# FE.net
KiCad netlist of a schematic drawn in Altium Designer
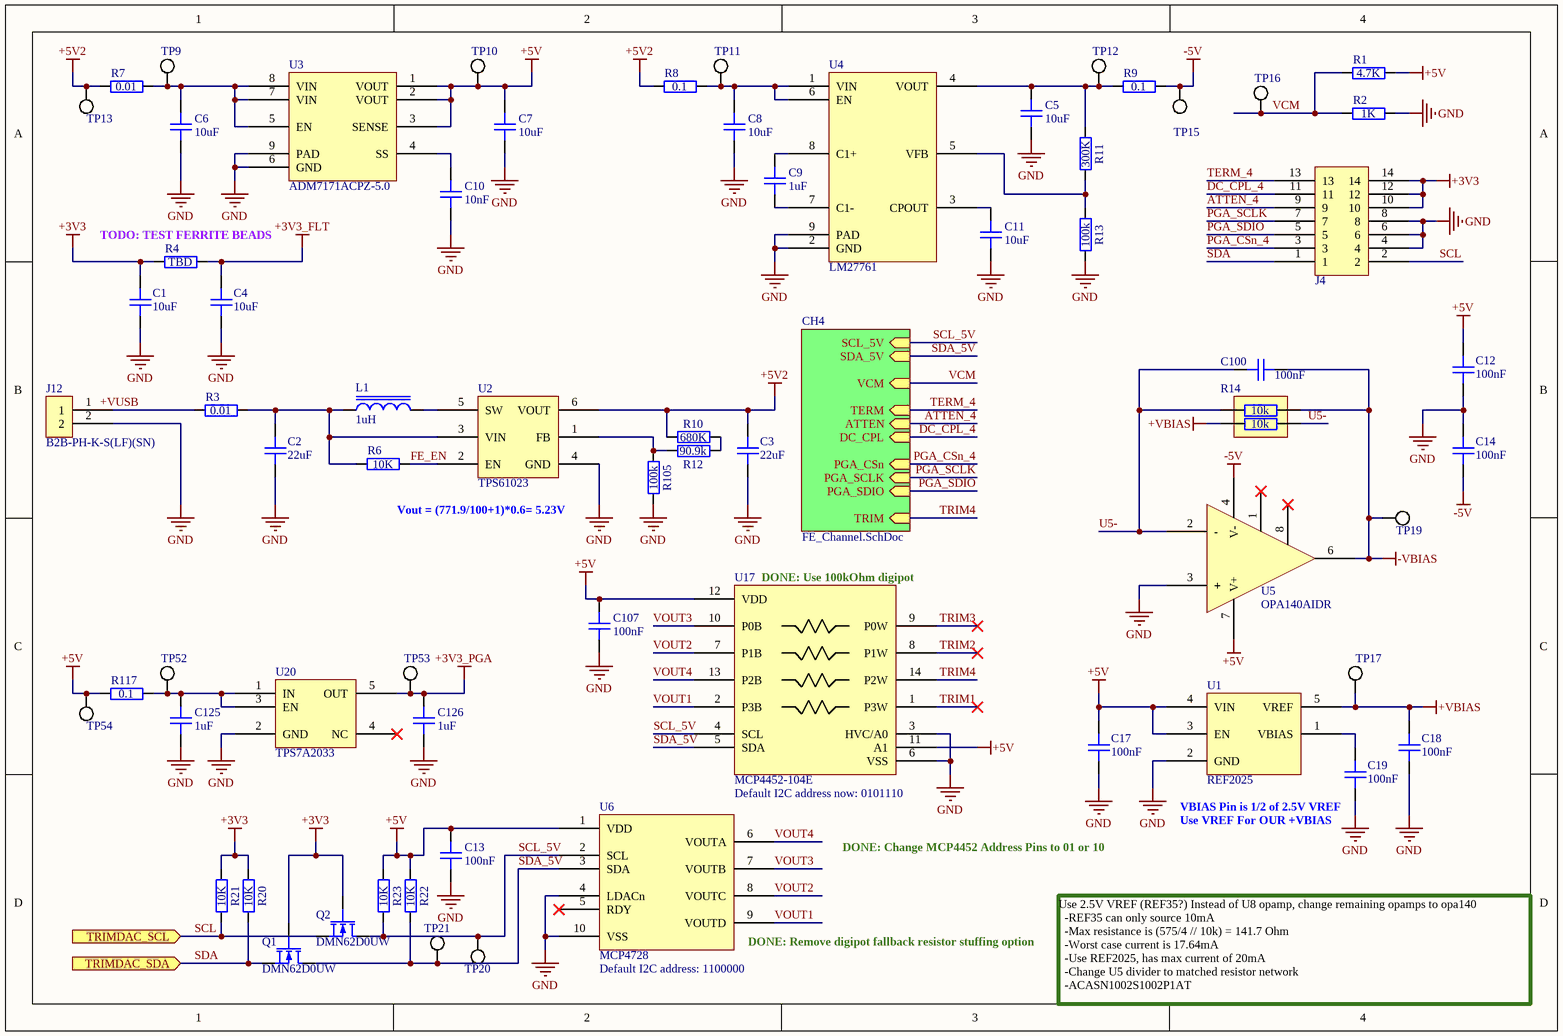
[diagram p0: FE.SchDoc]

(export (version "E")
  (design (tool "Eeschema 10.0.6"))
  (components
    (comp (ref "C1")
      (value "10uF")
      (footprint "GEN_C_0603")
      (fields
        (field (name "MANUFACTURER") "Murata")
        (field (name "HOUSE PART NUMBER") "C-10uF-0603-002")
        (field (name "MANUFACTURER PART NUMBER") "GRM188R61A106ME69D")
      )
      (libsource (lib "DSO") (part "CAP 10uF 10V X5R 0603"))
    )
    (comp (ref "C2")
      (value "22uF")
      (footprint "GEN_C_0805")
      (fields
        (field (name "HOUSE PART NUMBER") "C-22uF-0805-002")
        (field (name "MANUFACTURER") "Murata")
        (field (name "MANUFACTURER PART NUMBER") "GRM21BR61E226ME44L")
      )
      (libsource (lib "DSO") (part "CAP 22uF 25V X5R 0805"))
    )
    (comp (ref "C3")
      (value "22uF")
      (footprint "GEN_C_0805")
      (fields
        (field (name "HOUSE PART NUMBER") "C-22uF-0805-002")
        (field (name "MANUFACTURER") "Murata")
        (field (name "MANUFACTURER PART NUMBER") "GRM21BR61E226ME44L")
      )
      (libsource (lib "DSO") (part "CAP 22uF 25V X5R 0805"))
    )
    (comp (ref "C4")
      (value "10uF")
      (footprint "GEN_C_0603")
      (fields
        (field (name "MANUFACTURER") "Murata")
        (field (name "HOUSE PART NUMBER") "C-10uF-0603-002")
        (field (name "MANUFACTURER PART NUMBER") "GRM188R61A106ME69D")
      )
      (libsource (lib "DSO") (part "CAP 10uF 10V X5R 0603"))
    )
    (comp (ref "C5")
      (value "10uF")
      (footprint "GEN_C_0603")
      (fields
        (field (name "HOUSE PART NUMBER") "C-10uF-0603-002")
        (field (name "MANUFACTURER") "Murata")
        (field (name "MANUFACTURER PART NUMBER") "GRM188R61A106ME69D")
      )
      (libsource (lib "DSO") (part "CAP 10uF 10V X5R 0603"))
    )
    (comp (ref "C6")
      (value "10uF")
      (footprint "GEN_C_0603")
      (fields
        (field (name "HOUSE PART NUMBER") "C-10uF-0603-002")
        (field (name "MANUFACTURER") "Murata")
        (field (name "MANUFACTURER PART NUMBER") "GRM188R61A106ME69D")
      )
      (libsource (lib "DSO") (part "CAP 10uF 10V X5R 0603"))
    )
    (comp (ref "C7")
      (value "10uF")
      (footprint "GEN_C_0603")
      (fields
        (field (name "HOUSE PART NUMBER") "C-10uF-0603-002")
        (field (name "MANUFACTURER") "Murata")
        (field (name "MANUFACTURER PART NUMBER") "GRM188R61A106ME69D")
      )
      (libsource (lib "DSO") (part "CAP 10uF 10V X5R 0603"))
    )
    (comp (ref "C8")
      (value "10uF")
      (footprint "GEN_C_0603")
      (fields
        (field (name "HOUSE PART NUMBER") "C-10uF-0603-002")
        (field (name "MANUFACTURER") "Murata")
        (field (name "MANUFACTURER PART NUMBER") "GRM188R61A106ME69D")
      )
      (libsource (lib "DSO") (part "CAP 10uF 10V X5R 0603"))
    )
    (comp (ref "C9")
      (value "1uF")
      (footprint "GEN_C_0402")
      (fields
        (field (name "MANUFACTURER") "Murata")
        (field (name "MANUFACTURER PART NUMBER") "GRM155R61E105KA12D")
      )
      (libsource (lib "DSO") (part "CAP 1uF 25V X5R 0402"))
    )
    (comp (ref "C10")
      (value "10nF")
      (footprint "GEN_C_0402")
      (fields
        (field (name "MANUFACTURER") "Murata")
        (field (name "HOUSE PART NUMBER") "C-10nF-0402-002")
        (field (name "MANUFACTURER PART NUMBER") "GRM155R71H103KA88J")
      )
      (libsource (lib "DSO") (part "CAP 10nF 50V X7R 0402"))
    )
    (comp (ref "C11")
      (value "10uF")
      (footprint "GEN_C_0603")
      (fields
        (field (name "HOUSE PART NUMBER") "C-10uF-0603-002")
        (field (name "MANUFACTURER") "Murata")
        (field (name "MANUFACTURER PART NUMBER") "GRM188R61A106ME69D")
      )
      (libsource (lib "DSO") (part "CAP 10uF 10V X5R 0603"))
    )
    (comp (ref "C12")
      (value "100nF")
      (footprint "GEN_C_0402")
      (fields
        (field (name "HOUSE PART NUMBER") "C-100nF-0402-002")
        (field (name "MANUFACTURER") "Murata")
        (field (name "MANUFACTURER PART NUMBER") "GCM155R71C104KA55D")
      )
      (libsource (lib "DSO") (part "CAP 100nF 16V X7R 0402"))
    )
    (comp (ref "C13")
      (value "100nF")
      (footprint "GEN_C_0402")
      (fields
        (field (name "HOUSE PART NUMBER") "C-100nF-0402-002")
        (field (name "MANUFACTURER") "Murata")
        (field (name "MANUFACTURER PART NUMBER") "GCM155R71C104KA55D")
      )
      (libsource (lib "DSO") (part "CAP 100nF 16V X7R 0402"))
    )
    (comp (ref "C14")
      (value "100nF")
      (footprint "GEN_C_0402")
      (fields
        (field (name "HOUSE PART NUMBER") "C-100nF-0402-002")
        (field (name "MANUFACTURER") "Murata")
        (field (name "MANUFACTURER PART NUMBER") "GCM155R71C104KA55D")
      )
      (libsource (lib "DSO") (part "CAP 100nF 16V X7R 0402"))
    )
    (comp (ref "C17")
      (value "100nF")
      (footprint "GEN_C_0402")
      (fields
        (field (name "HOUSE PART NUMBER") "C-100nF-0402-002")
        (field (name "MANUFACTURER") "Murata")
        (field (name "MANUFACTURER PART NUMBER") "GCM155R71C104KA55D")
      )
      (libsource (lib "DSO") (part "CAP 100nF 16V X7R 0402"))
    )
    (comp (ref "C18")
      (value "100nF")
      (footprint "GEN_C_0402")
      (fields
        (field (name "HOUSE PART NUMBER") "C-100nF-0402-002")
        (field (name "MANUFACTURER") "Murata")
        (field (name "MANUFACTURER PART NUMBER") "GCM155R71C104KA55D")
      )
      (libsource (lib "DSO") (part "CAP 100nF 16V X7R 0402"))
    )
    (comp (ref "C19")
      (value "100nF")
      (footprint "GEN_C_0402")
      (fields
        (field (name "HOUSE PART NUMBER") "C-100nF-0402-002")
        (field (name "MANUFACTURER") "Murata")
        (field (name "MANUFACTURER PART NUMBER") "GCM155R71C104KA55D")
      )
      (libsource (lib "DSO") (part "CAP 100nF 16V X7R 0402"))
    )
    (comp (ref "C100")
      (value "100nF")
      (footprint "GEN_C_0402")
      (fields
        (field (name "HOUSE PART NUMBER") "C-100nF-0402-002")
        (field (name "MANUFACTURER") "Murata")
        (field (name "MANUFACTURER PART NUMBER") "GCM155R71C104KA55D")
      )
      (libsource (lib "DSO") (part "CAP 100nF 16V X7R 0402"))
    )
    (comp (ref "C107")
      (value "100nF")
      (footprint "GEN_C_0402")
      (fields
        (field (name "HOUSE PART NUMBER") "C-100nF-0402-002")
        (field (name "MANUFACTURER") "Murata")
        (field (name "MANUFACTURER PART NUMBER") "GCM155R71C104KA55D")
      )
      (libsource (lib "DSO") (part "CAP 100nF 16V X7R 0402"))
    )
    (comp (ref "C125")
      (value "1uF")
      (footprint "GEN_C_0402")
      (fields
        (field (name "MANUFACTURER") "Murata")
        (field (name "MANUFACTURER PART NUMBER") "GRM155R61E105KA12D")
      )
      (libsource (lib "DSO") (part "CAP 1uF 25V X5R 0402"))
    )
    (comp (ref "C126")
      (value "1uF")
      (footprint "GEN_C_0402")
      (fields
        (field (name "MANUFACTURER") "Murata")
        (field (name "MANUFACTURER PART NUMBER") "GRM155R61E105KA12D")
      )
      (libsource (lib "DSO") (part "CAP 1uF 25V X5R 0402"))
    )
    (comp (ref "J4")
      (value "2.54mm 2X7 Pin TH")
      (footprint "GEN_2.54mm_2X7_Pin_TH_RA")
      (libsource (lib "DSO") (part "CONN 2.54mm 2X7 Pin TH RA"))
    )
    (comp (ref "J12")
      (value "B2B-PH-K-S(LF)(SN)")
      (footprint "JST_B2B-PH-K-S(LF)(SN)")
      (fields
        (field (name "MANUFACTURER") "JST")
        (field (name "MANUFACTURER PART NUMBER") "B2B-PH-K-S-LF-SN")
      )
      (libsource (lib "DSO") (part "CONN JST PH 2 Pin TH"))
    )
    (comp (ref "L1")
      (value "1uH")
      (footprint "GEN_L_1210")
      (fields
        (field (name "MANUFACTURER") "Murata")
        (field (name "MANUFACTURER PART NUMBER") "1277AS-H-1R0M=P2")
      )
      (libsource (lib "DSO") (part "IND 1uH 3.1A 45 MOHM 1210"))
    )
    (comp (ref "Q1")
      (value "DMN62D0UW")
      (footprint "GEN_SOT_323")
      (fields (field (name "HOUSE PART NUMBER") "DMN62D0UW-7") (field (name "MANUFACTURER") "Diodes"))
      (libsource (lib "DSO") (part "NMOS DMN62D0UW"))
    )
    (comp (ref "Q2")
      (value "DMN62D0UW")
      (footprint "GEN_SOT_323")
      (fields (field (name "HOUSE PART NUMBER") "DMN62D0UW-7") (field (name "MANUFACTURER") "Diodes"))
      (libsource (lib "DSO") (part "NMOS DMN62D0UW"))
    )
    (comp (ref "R1")
      (value "4.7K")
      (footprint "GEN_R_0402")
      (fields
        (field (name "TOLERANCE") "1%")
        (field (name "MANUFACTURER") "Panasonic")
        (field (name "MANUFACTURER PART NUMBER") "ERJ-2RKF4701X")
      )
      (libsource (lib "DSO") (part "RES 4.7K OHM 1% 1/10W 0402"))
    )
    (comp (ref "R2")
      (value "1K")
      (footprint "GEN_R_0402")
      (fields
        (field (name "TOLERANCE") "1%")
        (field (name "MANUFACTURER") "Yageo")
        (field (name "HOUSE PART NUMBER") "R-1K-0402-1%-001")
      )
      (libsource (lib "DSO") (part "RES 1K OHM 1% 1/10W 0402"))
    )
    (comp (ref "R3")
      (value "0.01")
      (footprint "GEN_R_0603")
      (fields
        (field (name "TOLERANCE") "1%")
        (field (name "HOUSE PART NUMBER") "R-0.01-0603-1%-001")
        (field (name "MANUFACTURER") "Susumu")
      )
      (libsource (lib "") (part "RES 0.01 OHM 1% 1/4W 0603_1"))
    )
    (comp (ref "R4") (value "TBD") (footprint "GEN_R_0603") (libsource (lib "DSO") (part "RES TBD 0603")))
    (comp (ref "R6")
      (value "10K")
      (footprint "GEN_R_0402")
      (fields
        (field (name "TOLERANCE") "1%")
        (field (name "MANUFACTURER") "Panasonic")
        (field (name "MANUFACTURER PART NUMBER") "ERJ-2RKF1002X")
      )
      (libsource (lib "") (part "RES 10K OHM 1% 1/10W 0402_1"))
    )
    (comp (ref "R7")
      (value "0.01")
      (footprint "GEN_R_0603")
      (fields
        (field (name "TOLERANCE") "1%")
        (field (name "HOUSE PART NUMBER") "R-0.01-0603-1%-001")
        (field (name "MANUFACTURER") "Susumu")
      )
      (libsource (lib "DSO") (part "RES 0.01 OHM 1% 1/4W 0603"))
    )
    (comp (ref "R8")
      (value "0.1")
      (footprint "GEN_R_0402")
      (fields
        (field (name "TOLERANCE") "1%")
        (field (name "MANUFACTURER") "Panasonic")
        (field (name "MANUFACTURER PART NUMBER") "ERJ-2BSFR10X")
      )
      (libsource (lib "DSO") (part "RES 0.1 OHM 1% 1/6W 0402"))
    )
    (comp (ref "R9")
      (value "0.1")
      (footprint "GEN_R_0402")
      (fields
        (field (name "TOLERANCE") "1%")
        (field (name "MANUFACTURER") "Panasonic")
        (field (name "MANUFACTURER PART NUMBER") "ERJ-2BSFR10X")
      )
      (libsource (lib "DSO") (part "RES 0.1 OHM 1% 1/6W 0402"))
    )
    (comp (ref "R10")
      (value "680K")
      (footprint "GEN_R_0402")
      (fields
        (field (name "TOLERANCE") "1%")
        (field (name "MANUFACTURER") "Yageo")
        (field (name "MANUFACTURER PART NUMBER") "RC0402FR-07681KL")
      )
      (libsource (lib "DSO") (part "RES 680K OHM 1% 1/16W 0402"))
    )
    (comp (ref "R11")
      (value "300K")
      (footprint "GEN_R_0402")
      (fields
        (field (name "TOLERANCE") "1%")
        (field (name "MANUFACTURER") "Panasonic")
        (field (name "MANUFACTURER PART NUMBER") "ERJ-2RKF3003X")
      )
      (libsource (lib "DSO") (part "RES 300K OHM 1% 1/10W 0402"))
    )
    (comp (ref "R12")
      (value "90.9k")
      (footprint "GEN_R_0402")
      (fields
        (field (name "TOLERANCE") "1%")
        (field (name "MANUFACTURER") "Yageo")
        (field (name "MANUFACTURER PART NUMBER") "RC0402FR-0790K9L")
      )
      (libsource (lib "DSO") (part "RES 90.9K OHM 1% 1/16W 0402"))
    )
    (comp (ref "R13")
      (value "100k")
      (footprint "GEN_R_0402")
      (fields
        (field (name "TOLERANCE") "1%")
        (field (name "HOUSE PART NUMBER") "R-100K-0402-1%-001")
        (field (name "MANUFACTURER") "Yageo")
      )
      (libsource (lib "DSO") (part "RES 100K OHM 1% 1/10W 0402"))
    )
    (comp (ref "R14")
      (value "10K")
      (footprint "GEN_R_2ARRAY_0606")
      (fields
        (field (name "TOLERANCE") "1%")
        (field (name "MANUFACTURER") "Vishay Beyschlag")
        (field (name "MANUFACTURER PART NUMBER") "ACASN1002S1002P1ATF1002X")
      )
      (libsource (lib "DSO") (part "RES ARRAY 2x 10K OHM 0.05% 0606"))
    )
    (comp (ref "R20")
      (value "10K")
      (footprint "GEN_R_0402")
      (fields
        (field (name "TOLERANCE") "1%")
        (field (name "MANUFACTURER") "Panasonic")
        (field (name "MANUFACTURER PART NUMBER") "ERJ-2RKF1002X")
      )
      (libsource (lib "DSO") (part "RES 10K OHM 1% 1/10W 0402"))
    )
    (comp (ref "R21")
      (value "10K")
      (footprint "GEN_R_0402")
      (fields
        (field (name "TOLERANCE") "1%")
        (field (name "MANUFACTURER") "Panasonic")
        (field (name "MANUFACTURER PART NUMBER") "ERJ-2RKF1002X")
      )
      (libsource (lib "DSO") (part "RES 10K OHM 1% 1/10W 0402"))
    )
    (comp (ref "R22")
      (value "10K")
      (footprint "GEN_R_0402")
      (fields
        (field (name "TOLERANCE") "1%")
        (field (name "MANUFACTURER") "Panasonic")
        (field (name "MANUFACTURER PART NUMBER") "ERJ-2RKF1002X")
      )
      (libsource (lib "DSO") (part "RES 10K OHM 1% 1/10W 0402"))
    )
    (comp (ref "R23")
      (value "10K")
      (footprint "GEN_R_0402")
      (fields
        (field (name "TOLERANCE") "1%")
        (field (name "MANUFACTURER") "Panasonic")
        (field (name "MANUFACTURER PART NUMBER") "ERJ-2RKF1002X")
      )
      (libsource (lib "DSO") (part "RES 10K OHM 1% 1/10W 0402"))
    )
    (comp (ref "R105")
      (value "100k")
      (footprint "GEN_R_0402")
      (fields
        (field (name "TOLERANCE") "1%")
        (field (name "HOUSE PART NUMBER") "R-100K-0402-1%-001")
        (field (name "MANUFACTURER") "Yageo")
      )
      (libsource (lib "DSO") (part "RES 100K OHM 1% 1/10W 0402"))
    )
    (comp (ref "R117")
      (value "0.1")
      (footprint "GEN_R_0402")
      (fields
        (field (name "TOLERANCE") "1%")
        (field (name "MANUFACTURER") "Panasonic")
        (field (name "MANUFACTURER PART NUMBER") "ERJ-2BSFR10X")
      )
      (libsource (lib "DSO") (part "RES 0.1 OHM 1% 1/6W 0402"))
    )
    (comp (ref "TP9") (value "PCB") (footprint "GEN_TP_PCB") (libsource (lib "DSO") (part "TP PCB 1mm")))
    (comp (ref "TP10") (value "PCB") (footprint "GEN_TP_PCB") (libsource (lib "DSO") (part "TP PCB 1mm")))
    (comp (ref "TP11") (value "PCB") (footprint "GEN_TP_PCB") (libsource (lib "DSO") (part "TP PCB 1mm")))
    (comp (ref "TP12") (value "PCB") (footprint "GEN_TP_PCB") (libsource (lib "DSO") (part "TP PCB 1mm")))
    (comp (ref "TP13") (value "PCB") (footprint "GEN_TP_PCB") (libsource (lib "DSO") (part "TP PCB 1mm")))
    (comp (ref "TP15") (value "PCB") (footprint "GEN_TP_PCB") (libsource (lib "DSO") (part "TP PCB 1mm")))
    (comp (ref "TP16") (value "PCB") (footprint "GEN_TP_PCB") (libsource (lib "DSO") (part "TP PCB 1mm")))
    (comp (ref "TP17") (value "PCB") (footprint "GEN_TP_PCB") (libsource (lib "DSO") (part "TP PCB 1mm")))
    (comp (ref "TP19") (value "PCB") (footprint "GEN_TP_PCB") (libsource (lib "DSO") (part "TP PCB 1mm")))
    (comp (ref "TP20") (value "PCB") (footprint "GEN_TP_PCB") (libsource (lib "DSO") (part "TP PCB 1mm")))
    (comp (ref "TP21") (value "PCB") (footprint "GEN_TP_PCB") (libsource (lib "DSO") (part "TP PCB 1mm")))
    (comp (ref "TP52") (value "PCB") (footprint "GEN_TP_PCB") (libsource (lib "DSO") (part "TP PCB 1mm")))
    (comp (ref "TP53") (value "PCB") (footprint "GEN_TP_PCB") (libsource (lib "DSO") (part "TP PCB 1mm")))
    (comp (ref "TP54") (value "PCB") (footprint "GEN_TP_PCB") (libsource (lib "DSO") (part "TP PCB 1mm")))
    (comp (ref "U1")
      (value "REF2025")
      (footprint "GEN_SOT23_5_950_2900X1600X1450")
      (libsource (lib "DSO") (part "IC VREF REF2025"))
    )
    (comp (ref "U2")
      (value "TPS61023")
      (footprint "TI_SOT563_DRL0006A")
      (fields
        (field (name "MANUFACTURER") "Texas Instruments")
        (field (name "MANUFACTURER PART NUMBER") "TPS61023DRLT")
      )
      (libsource (lib "DSO") (part "IC BOOST TPS61023"))
    )
    (comp (ref "U3")
      (value "ADM7171ACPZ-5.0")
      (footprint "AD_DFN8_CP-8-21")
      (fields
        (field (name "MANUFACTURER") "Analog Devices")
        (field (name "MANUFACTURER PART NUMBER") "ADM7171ACPZ-5.0-R7")
      )
      (libsource (lib "DSO") (part "IC LDO ADM7171ACPZ-5.0"))
    )
    (comp (ref "U4")
      (value "LM27761")
      (footprint "TI_WSON8_DSG0008A")
      (fields
        (field (name "MANUFACTURER") "Texas Instruments")
        (field (name "MANUFACTURER PART NUMBER") "LM27761DSGR")
      )
      (libsource (lib "DSO") (part "IC CPUMP LM27761"))
    )
    (comp (ref "U5")
      (value "OPA140AIDR")
      (footprint "TI_SOIC8_D0008A")
      (fields (field (name "MANUFACTURER") "Texas Instruments"))
      (libsource (lib "DSO") (part "IC OPAMP OPA140"))
    )
    (comp (ref "U6")
      (value "MCP4728")
      (footprint "MC_MSOP10_UN")
      (fields (field (name "MANUFACTURER") "Microchip"))
      (libsource (lib "DSO") (part "IC DAC QUAD MCP4728"))
    )
    (comp (ref "U17")
      (value "MCP4452-104E")
      (footprint "MC_TSSOP14")
      (fields (field (name "MANUFACTURER") "Microchip"))
      (libsource (lib "DSO") (part "IC DIGIPOT QUAD MCP4452-104E"))
    )
    (comp (ref "U20")
      (value "TPS7A2033")
      (footprint "GEN_SOT23_5_950_2900X1600X1450")
      (fields
        (field (name "MANUFACTURER") "Texas Instruments")
        (field (name "MANUFACTURER PART NUMBER") "TPS7A2033PDBVR")
      )
      (libsource (lib "DSO") (part "IC LDO TPS7A2033"))
    )
  )
  (nets
    (net (code "1") (name "+3V3") (class "Default")
      (node (ref "C1") (pin "2") (pinfunction "2_2") (pintype "passive"))
      (node (ref "J4") (pin "10") (pinfunction "10_10") (pintype "passive"))
      (node (ref "J4") (pin "12") (pinfunction "12_12") (pintype "passive"))
      (node (ref "J4") (pin "14") (pinfunction "14_14") (pintype "passive"))
      (node (ref "Q1") (pin "2") (pinfunction "G_2") (pintype "passive"))
      (node (ref "Q2") (pin "2") (pinfunction "G_2") (pintype "passive"))
      (node (ref "R20") (pin "2") (pinfunction "2_2") (pintype "passive"))
      (node (ref "R21") (pin "2") (pinfunction "2_2") (pintype "passive"))
      (node (ref "R4") (pin "1") (pinfunction "1_1") (pintype "passive"))
    )
    (net (code "2") (name "+3V3_FLT") (class "Default")
      (node (ref "C4") (pin "2") (pinfunction "2_2") (pintype "passive"))
      (node (ref "R4") (pin "2") (pinfunction "2_2") (pintype "passive"))
    )
    (net (code "3") (name "+3V3_PGA") (class "Default")
      (node (ref "C126") (pin "2") (pinfunction "2_2") (pintype "passive"))
      (node (ref "TP53") (pin "1") (pinfunction "1_1") (pintype "passive"))
      (node (ref "U20") (pin "5") (pinfunction "OUT_5") (pintype "power_in"))
    )
    (net (code "4") (name "+5V") (class "Default")
      (node (ref "C107") (pin "2") (pinfunction "2_2") (pintype "passive"))
      (node (ref "C12") (pin "1") (pinfunction "1_1") (pintype "passive"))
      (node (ref "C13") (pin "2") (pinfunction "2_2") (pintype "passive"))
      (node (ref "C17") (pin "1") (pinfunction "1_1") (pintype "passive"))
      (node (ref "C7") (pin "2") (pinfunction "2_2") (pintype "passive"))
      (node (ref "R1") (pin "2") (pinfunction "2_2") (pintype "passive"))
      (node (ref "R117") (pin "1") (pinfunction "1_1") (pintype "passive"))
      (node (ref "R22") (pin "2") (pinfunction "2_2") (pintype "passive"))
      (node (ref "R23") (pin "2") (pinfunction "2_2") (pintype "passive"))
      (node (ref "TP10") (pin "1") (pinfunction "1_1") (pintype "passive"))
      (node (ref "TP54") (pin "1") (pinfunction "1_1") (pintype "passive"))
      (node (ref "U1") (pin "3") (pinfunction "EN_3") (pintype "passive"))
      (node (ref "U1") (pin "4") (pinfunction "VIN_4") (pintype "passive"))
      (node (ref "U17") (pin "11") (pinfunction "A1_11") (pintype "passive"))
      (node (ref "U17") (pin "12") (pinfunction "VDD_12") (pintype "power_in"))
      (node (ref "U3") (pin "1") (pinfunction "VOUT_1") (pintype "power_in"))
      (node (ref "U3") (pin "2") (pinfunction "VOUT_2") (pintype "power_in"))
      (node (ref "U3") (pin "3") (pinfunction "SENSE_3") (pintype "passive"))
      (node (ref "U5") (pin "7") (pinfunction "V+_7") (pintype "passive"))
      (node (ref "U6") (pin "1") (pinfunction "VDD_1") (pintype "power_in"))
    )
    (net (code "5") (name "+5V2") (class "Default")
      (node (ref "C3") (pin "2") (pinfunction "2_2") (pintype "passive"))
      (node (ref "R10") (pin "2") (pinfunction "2_2") (pintype "passive"))
      (node (ref "R7") (pin "1") (pinfunction "1_1") (pintype "passive"))
      (node (ref "R8") (pin "1") (pinfunction "1_1") (pintype "passive"))
      (node (ref "TP13") (pin "1") (pinfunction "1_1") (pintype "passive"))
      (node (ref "U2") (pin "6") (pinfunction "VOUT_6") (pintype "passive"))
    )
    (net (code "6") (name "+VBIAS") (class "Default")
      (node (ref "C18") (pin "1") (pinfunction "1_1") (pintype "passive"))
      (node (ref "R14") (pin "2") (pinfunction "2_2") (pintype "passive"))
      (node (ref "TP17") (pin "1") (pinfunction "1_1") (pintype "passive"))
      (node (ref "U1") (pin "5") (pinfunction "VREF_5") (pintype "passive"))
    )
    (net (code "7") (name "-5V") (class "Default")
      (node (ref "C14") (pin "2") (pinfunction "2_2") (pintype "passive"))
      (node (ref "R9") (pin "2") (pinfunction "2_2") (pintype "passive"))
      (node (ref "TP15") (pin "1") (pinfunction "1_1") (pintype "passive"))
      (node (ref "U5") (pin "4") (pinfunction "V-_4") (pintype "passive"))
    )
    (net (code "8") (name "-VBIAS") (class "Default")
      (node (ref "C100") (pin "1") (pinfunction "1_1") (pintype "passive"))
      (node (ref "R14") (pin "4") (pinfunction "4_4") (pintype "passive"))
      (node (ref "TP19") (pin "1") (pinfunction "1_1") (pintype "passive"))
      (node (ref "U5") (pin "6") (pinfunction "OUT_6") (pintype "passive"))
    )
    (net (code "9") (name "/+VUSB") (class "Default")
      (node (ref "J12") (pin "1") (pinfunction "1_1") (pintype "passive"))
      (node (ref "R3") (pin "2") (pinfunction "2_2") (pintype "passive"))
    )
    (net (code "10") (name "/ATTEN_4") (class "Default")
      (node (ref "J4") (pin "9") (pinfunction "9_9") (pintype "passive"))
    )
    (net (code "11") (name "/DC_CPL_4") (class "Default")
      (node (ref "J4") (pin "11") (pinfunction "11_11") (pintype "passive"))
    )
    (net (code "12") (name "/FE_EN") (class "Default")
      (node (ref "R6") (pin "1") (pinfunction "1_1") (pintype "passive"))
      (node (ref "U2") (pin "2") (pinfunction "EN_2") (pintype "passive"))
    )
    (net (code "13") (name "/PGA_CSn_4") (class "Default")
      (node (ref "J4") (pin "3") (pinfunction "3_3") (pintype "passive"))
    )
    (net (code "14") (name "/PGA_SCLK") (class "Default")
      (node (ref "J4") (pin "7") (pinfunction "7_7") (pintype "passive"))
    )
    (net (code "15") (name "/PGA_SDIO") (class "Default")
      (node (ref "J4") (pin "5") (pinfunction "5_5") (pintype "passive"))
    )
    (net (code "16") (name "/SCL") (class "Default")
      (node (ref "J4") (pin "2") (pinfunction "2_2") (pintype "passive"))
      (node (ref "Q2") (pin "3") (pinfunction "S_3") (pintype "passive"))
      (node (ref "R21") (pin "1") (pinfunction "1_1") (pintype "passive"))
    )
    (net (code "17") (name "/SCL_5V") (class "Default")
      (node (ref "Q2") (pin "1") (pinfunction "D_1") (pintype "passive"))
      (node (ref "R23") (pin "1") (pinfunction "1_1") (pintype "passive"))
      (node (ref "TP20") (pin "1") (pinfunction "1_1") (pintype "passive"))
      (node (ref "U17") (pin "4") (pinfunction "SCL_4") (pintype "passive"))
      (node (ref "U6") (pin "2") (pinfunction "SCL_2") (pintype "passive"))
    )
    (net (code "18") (name "/SDA") (class "Default")
      (node (ref "J4") (pin "1") (pinfunction "1_1") (pintype "passive"))
      (node (ref "Q1") (pin "3") (pinfunction "S_3") (pintype "passive"))
      (node (ref "R20") (pin "1") (pinfunction "1_1") (pintype "passive"))
    )
    (net (code "19") (name "/SDA_5V") (class "Default")
      (node (ref "Q1") (pin "1") (pinfunction "D_1") (pintype "passive"))
      (node (ref "R22") (pin "1") (pinfunction "1_1") (pintype "passive"))
      (node (ref "TP21") (pin "1") (pinfunction "1_1") (pintype "passive"))
      (node (ref "U17") (pin "5") (pinfunction "SDA_5") (pintype "passive"))
      (node (ref "U6") (pin "3") (pinfunction "SDA_3") (pintype "passive"))
    )
    (net (code "20") (name "/TERM_4") (class "Default")
      (node (ref "J4") (pin "13") (pinfunction "13_13") (pintype "passive"))
    )
    (net (code "21") (name "/TRIM1") (class "Default")
      (node (ref "U17") (pin "1") (pinfunction "P3W_1") (pintype "passive+no_connect"))
    )
    (net (code "22") (name "/TRIM2") (class "Default")
      (node (ref "U17") (pin "8") (pinfunction "P1W_8") (pintype "passive+no_connect"))
    )
    (net (code "23") (name "/TRIM3") (class "Default")
      (node (ref "U17") (pin "9") (pinfunction "P0W_9") (pintype "passive+no_connect"))
    )
    (net (code "24") (name "/TRIM4") (class "Default")
      (node (ref "U17") (pin "14") (pinfunction "P2W_14") (pintype "passive"))
    )
    (net (code "25") (name "/U5-") (class "Default")
      (node (ref "C100") (pin "2") (pinfunction "2_2") (pintype "passive"))
      (node (ref "R14") (pin "1") (pinfunction "1_1") (pintype "passive"))
      (node (ref "R14") (pin "3") (pinfunction "3_3") (pintype "passive"))
      (node (ref "U5") (pin "2") (pinfunction "-_2") (pintype "passive"))
    )
    (net (code "26") (name "/VCM") (class "Default")
      (node (ref "R1") (pin "1") (pinfunction "1_1") (pintype "passive"))
      (node (ref "R2") (pin "1") (pinfunction "1_1") (pintype "passive"))
      (node (ref "TP16") (pin "1") (pinfunction "1_1") (pintype "passive"))
    )
    (net (code "27") (name "/VOUT1") (class "Default")
      (node (ref "U17") (pin "2") (pinfunction "P3B_2") (pintype "passive"))
      (node (ref "U6") (pin "9") (pinfunction "VOUTD_9") (pintype "passive"))
    )
    (net (code "28") (name "/VOUT2") (class "Default")
      (node (ref "U17") (pin "7") (pinfunction "P1B_7") (pintype "passive"))
      (node (ref "U6") (pin "8") (pinfunction "VOUTC_8") (pintype "passive"))
    )
    (net (code "29") (name "/VOUT3") (class "Default")
      (node (ref "U17") (pin "10") (pinfunction "P0B_10") (pintype "passive"))
      (node (ref "U6") (pin "7") (pinfunction "VOUTB_7") (pintype "passive"))
    )
    (net (code "30") (name "/VOUT4") (class "Default")
      (node (ref "U17") (pin "13") (pinfunction "P2B_13") (pintype "passive"))
      (node (ref "U6") (pin "6") (pinfunction "VOUTA_6") (pintype "passive"))
    )
    (net (code "31") (name "GND") (class "Default")
      (node (ref "C1") (pin "1") (pinfunction "1_1") (pintype "passive"))
      (node (ref "C10") (pin "1") (pinfunction "1_1") (pintype "passive"))
      (node (ref "C107") (pin "1") (pinfunction "1_1") (pintype "passive"))
      (node (ref "C11") (pin "1") (pinfunction "1_1") (pintype "passive"))
      (node (ref "C12") (pin "2") (pinfunction "2_2") (pintype "passive"))
      (node (ref "C125") (pin "1") (pinfunction "1_1") (pintype "passive"))
      (node (ref "C126") (pin "1") (pinfunction "1_1") (pintype "passive"))
      (node (ref "C13") (pin "1") (pinfunction "1_1") (pintype "passive"))
      (node (ref "C14") (pin "1") (pinfunction "1_1") (pintype "passive"))
      (node (ref "C17") (pin "2") (pinfunction "2_2") (pintype "passive"))
      (node (ref "C18") (pin "2") (pinfunction "2_2") (pintype "passive"))
      (node (ref "C19") (pin "1") (pinfunction "1_1") (pintype "passive"))
      (node (ref "C2") (pin "1") (pinfunction "1_1") (pintype "passive"))
      (node (ref "C3") (pin "1") (pinfunction "1_1") (pintype "passive"))
      (node (ref "C4") (pin "1") (pinfunction "1_1") (pintype "passive"))
      (node (ref "C5") (pin "1") (pinfunction "1_1") (pintype "passive"))
      (node (ref "C6") (pin "1") (pinfunction "1_1") (pintype "passive"))
      (node (ref "C7") (pin "1") (pinfunction "1_1") (pintype "passive"))
      (node (ref "C8") (pin "1") (pinfunction "1_1") (pintype "passive"))
      (node (ref "J12") (pin "2") (pinfunction "2_2") (pintype "passive"))
      (node (ref "J4") (pin "4") (pinfunction "4_4") (pintype "passive"))
      (node (ref "J4") (pin "6") (pinfunction "6_6") (pintype "passive"))
      (node (ref "J4") (pin "8") (pinfunction "8_8") (pintype "passive"))
      (node (ref "R105") (pin "1") (pinfunction "1_1") (pintype "passive"))
      (node (ref "R13") (pin "1") (pinfunction "1_1") (pintype "passive"))
      (node (ref "R2") (pin "2") (pinfunction "2_2") (pintype "passive"))
      (node (ref "U1") (pin "2") (pinfunction "GND_2") (pintype "passive"))
      (node (ref "U17") (pin "3") (pinfunction "HVC/A0_3") (pintype "passive"))
      (node (ref "U17") (pin "6") (pinfunction "VSS_6") (pintype "power_in"))
      (node (ref "U2") (pin "4") (pinfunction "GND_4") (pintype "power_in"))
      (node (ref "U20") (pin "2") (pinfunction "GND_2") (pintype "power_in"))
      (node (ref "U3") (pin "6") (pinfunction "GND_6") (pintype "power_in"))
      (node (ref "U3") (pin "9") (pinfunction "PAD_9") (pintype "passive"))
      (node (ref "U4") (pin "2") (pinfunction "GND_2") (pintype "power_in"))
      (node (ref "U4") (pin "9") (pinfunction "PAD_9") (pintype "power_in"))
      (node (ref "U5") (pin "3") (pinfunction "+_3") (pintype "passive"))
      (node (ref "U6") (pin "10") (pinfunction "VSS_10") (pintype "power_in"))
      (node (ref "U6") (pin "4") (pinfunction "LDACn_4") (pintype "passive"))
    )
    (net (code "32") (name "Net-(R10-Pad1)") (class "Default")
      (node (ref "R10") (pin "1") (pinfunction "1_1") (pintype "passive"))
      (node (ref "R12") (pin "2") (pinfunction "2_2") (pintype "passive"))
    )
    (net (code "33") (name "Net-(U1-VBIAS)") (class "Default")
      (node (ref "C19") (pin "2") (pinfunction "2_2") (pintype "passive"))
      (node (ref "U1") (pin "1") (pinfunction "VBIAS_1") (pintype "power_in"))
    )
    (net (code "34") (name "Net-(U2-FB)") (class "Default")
      (node (ref "R105") (pin "2") (pinfunction "2_2") (pintype "passive"))
      (node (ref "R12") (pin "1") (pinfunction "1_1") (pintype "passive"))
      (node (ref "U2") (pin "1") (pinfunction "FB_1") (pintype "passive"))
    )
    (net (code "35") (name "Net-(U2-SW)") (class "Default")
      (node (ref "L1") (pin "2") (pinfunction "2_2") (pintype "passive"))
      (node (ref "U2") (pin "5") (pinfunction "SW_5") (pintype "passive"))
    )
    (net (code "36") (name "Net-(U2-VIN)") (class "Default")
      (node (ref "C2") (pin "2") (pinfunction "2_2") (pintype "passive"))
      (node (ref "L1") (pin "1") (pinfunction "1_1") (pintype "passive"))
      (node (ref "R3") (pin "1") (pinfunction "1_1") (pintype "passive"))
      (node (ref "R6") (pin "2") (pinfunction "2_2") (pintype "passive"))
      (node (ref "U2") (pin "3") (pinfunction "VIN_3") (pintype "power_in"))
    )
    (net (code "37") (name "Net-(U3-EN)") (class "Default")
      (node (ref "C6") (pin "2") (pinfunction "2_2") (pintype "passive"))
      (node (ref "R7") (pin "2") (pinfunction "2_2") (pintype "passive"))
      (node (ref "TP9") (pin "1") (pinfunction "1_1") (pintype "passive"))
      (node (ref "U3") (pin "5") (pinfunction "EN_5") (pintype "passive"))
      (node (ref "U3") (pin "7") (pinfunction "VIN_7") (pintype "power_in"))
      (node (ref "U3") (pin "8") (pinfunction "VIN_8") (pintype "power_in"))
    )
    (net (code "38") (name "Net-(U3-SS)") (class "Default")
      (node (ref "C10") (pin "2") (pinfunction "2_2") (pintype "passive"))
      (node (ref "U3") (pin "4") (pinfunction "SS_4") (pintype "passive"))
    )
    (net (code "39") (name "Net-(U4-C1+)") (class "Default")
      (node (ref "C9") (pin "2") (pinfunction "2_2") (pintype "passive"))
      (node (ref "U4") (pin "8") (pinfunction "C1+_8") (pintype "passive"))
    )
    (net (code "40") (name "Net-(U4-C1-)") (class "Default")
      (node (ref "C9") (pin "1") (pinfunction "1_1") (pintype "passive"))
      (node (ref "U4") (pin "7") (pinfunction "C1-_7") (pintype "passive"))
    )
    (net (code "41") (name "Net-(U4-CPOUT)") (class "Default")
      (node (ref "C11") (pin "2") (pinfunction "2_2") (pintype "passive"))
      (node (ref "U4") (pin "3") (pinfunction "CPOUT_3") (pintype "passive"))
    )
    (net (code "42") (name "Net-(U4-EN)") (class "Default")
      (node (ref "C8") (pin "2") (pinfunction "2_2") (pintype "passive"))
      (node (ref "R8") (pin "2") (pinfunction "2_2") (pintype "passive"))
      (node (ref "TP11") (pin "1") (pinfunction "1_1") (pintype "passive"))
      (node (ref "U4") (pin "1") (pinfunction "VIN_1") (pintype "power_in"))
      (node (ref "U4") (pin "6") (pinfunction "EN_6") (pintype "passive"))
    )
    (net (code "43") (name "Net-(U4-VFB)") (class "Default")
      (node (ref "R11") (pin "1") (pinfunction "1_1") (pintype "passive"))
      (node (ref "R13") (pin "2") (pinfunction "2_2") (pintype "passive"))
      (node (ref "U4") (pin "5") (pinfunction "VFB_5") (pintype "passive"))
    )
    (net (code "44") (name "Net-(U4-VOUT)") (class "Default")
      (node (ref "C5") (pin "2") (pinfunction "2_2") (pintype "passive"))
      (node (ref "R11") (pin "2") (pinfunction "2_2") (pintype "passive"))
      (node (ref "R9") (pin "1") (pinfunction "1_1") (pintype "passive"))
      (node (ref "TP12") (pin "1") (pinfunction "1_1") (pintype "passive"))
      (node (ref "U4") (pin "4") (pinfunction "VOUT_4") (pintype "power_in"))
    )
    (net (code "45") (name "Net-(U20-EN)") (class "Default")
      (node (ref "C125") (pin "2") (pinfunction "2_2") (pintype "passive"))
      (node (ref "R117") (pin "2") (pinfunction "2_2") (pintype "passive"))
      (node (ref "TP52") (pin "1") (pinfunction "1_1") (pintype "passive"))
      (node (ref "U20") (pin "1") (pinfunction "IN_1") (pintype "power_in"))
      (node (ref "U20") (pin "3") (pinfunction "EN_3") (pintype "passive"))
    )
    (net (code "46") (name "unconnected-(U5-N1-Pad1)") (class "Default")
      (node (ref "U5") (pin "1") (pinfunction "N1_1") (pintype "passive+no_connect"))
    )
    (net (code "47") (name "unconnected-(U5-N2-Pad8)") (class "Default")
      (node (ref "U5") (pin "8") (pinfunction "N2_8") (pintype "passive+no_connect"))
    )
    (net (code "48") (name "unconnected-(U6-RDY-Pad5)") (class "Default")
      (node (ref "U6") (pin "5") (pinfunction "RDY_5") (pintype "passive+no_connect"))
    )
    (net (code "49") (name "unconnected-(U20-NC-Pad4)") (class "Default")
      (node (ref "U20") (pin "4") (pinfunction "NC_4") (pintype "passive+no_connect"))
    )
  )
)
